# 280109_Button_PCB_4_0.net
KiCad netlist of a schematic drawn in EAGLE
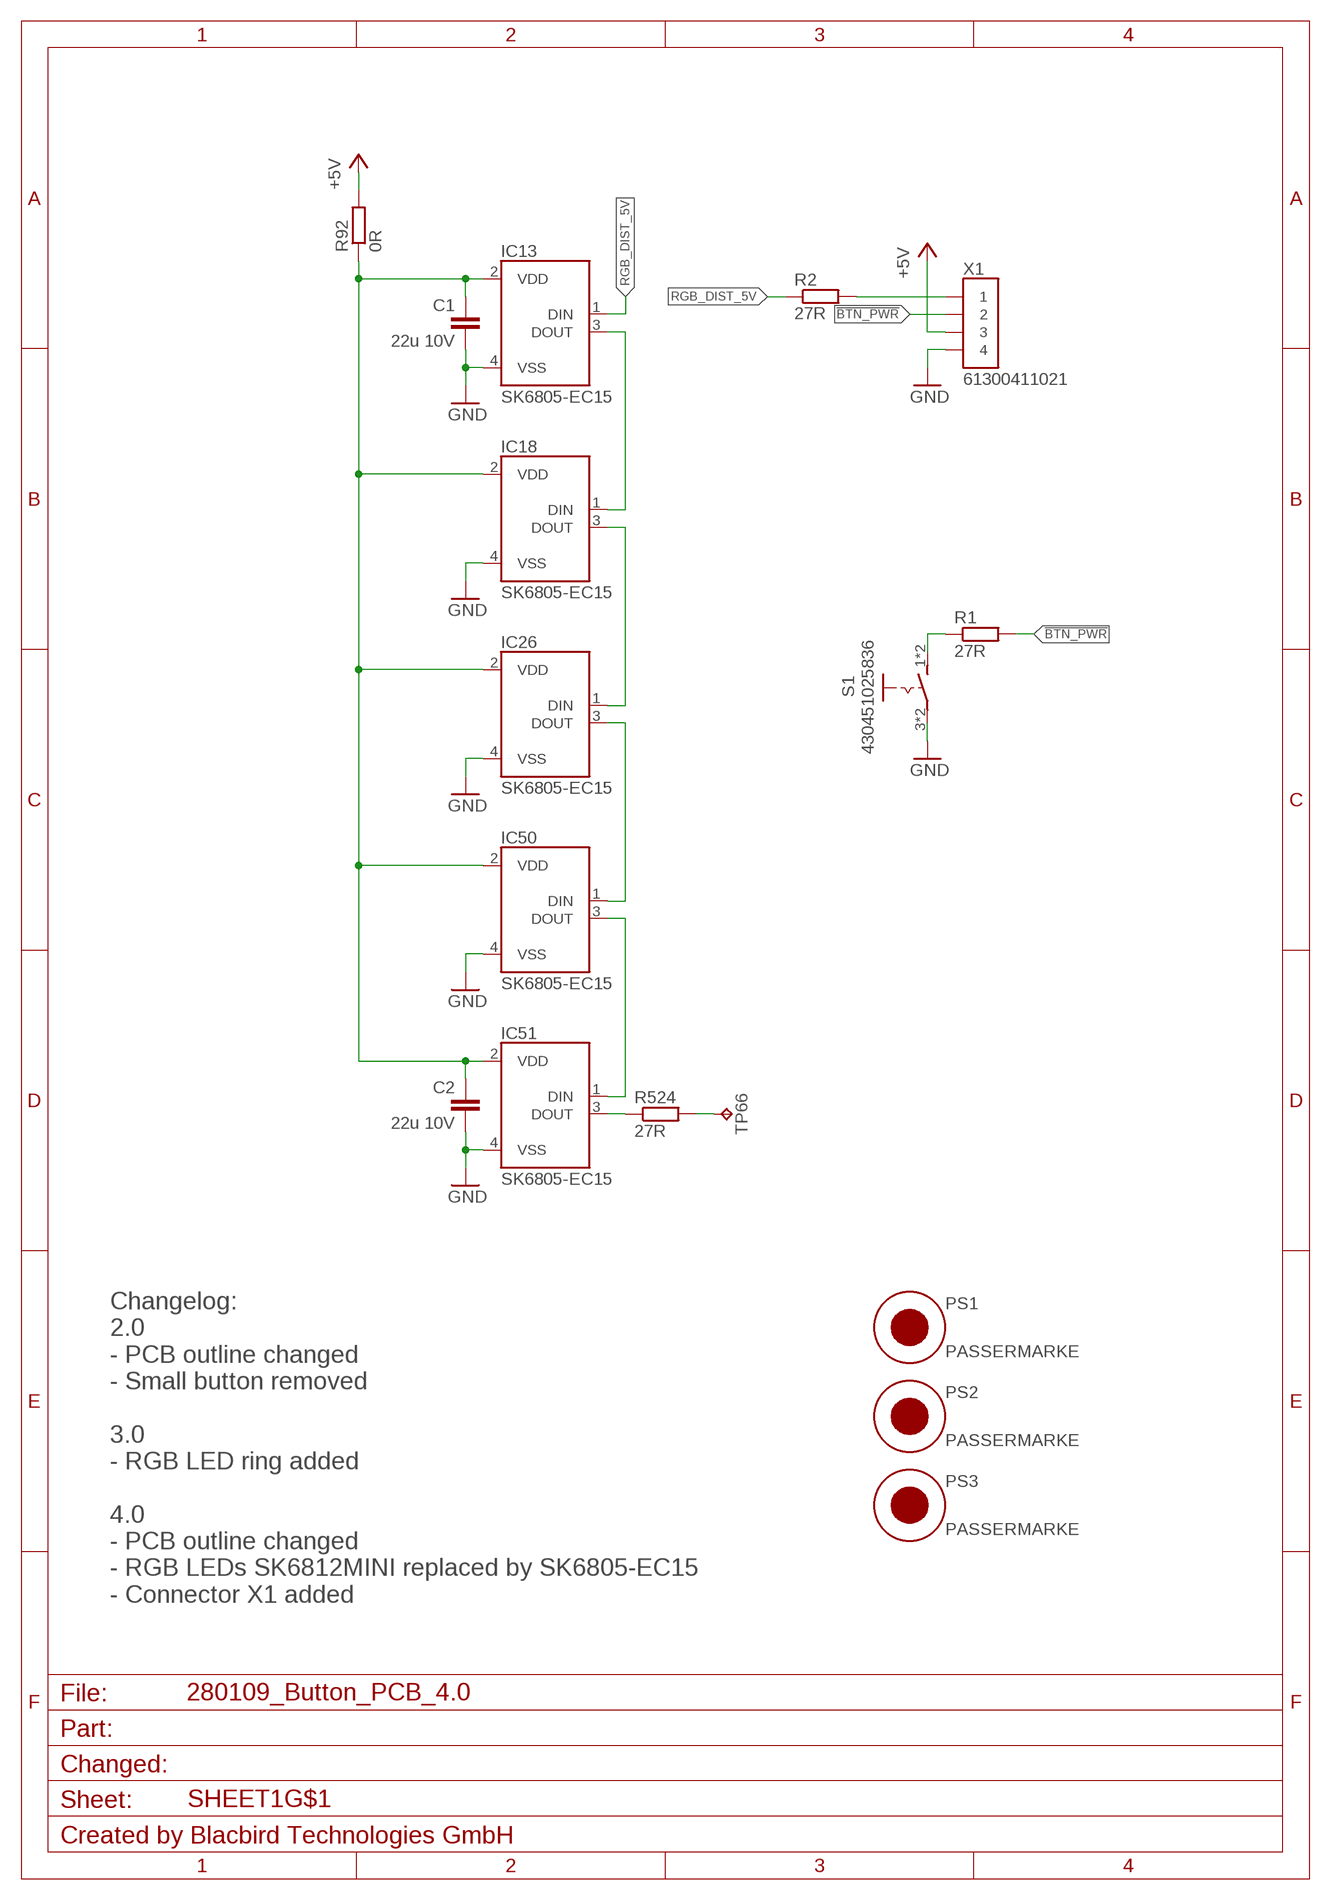
[diagram p0: schematic, sheet 1]

(export (version "E")
  (design (tool "Eeschema 10.0.6"))
  (components
    (comp (ref "C1")
      (value "22u 10V")
      (footprint "eagle-import:C0805")
      (fields (field (name "TOLERANCE") "±20 %") (field (name "VOLTAGE") "10.0 V"))
      (libsource (lib "eagle-import") (part "C-EUC0805"))
    )
    (comp (ref "C2")
      (value "22u 10V")
      (footprint "eagle-import:C0805")
      (fields (field (name "TOLERANCE") "±20 %") (field (name "VOLTAGE") "10.0 V"))
      (libsource (lib "eagle-import") (part "C-EUC0805"))
    )
    (comp (ref "IC13")
      (value "SK6805-EC15")
      (footprint "eagle-import:SK6805-EC_IPIXEL")
      (fields (field (name "MANUFACTURER") "IPIXELS") (field (name "VOLTAGE") "5.5 V"))
      (libsource (lib "eagle-import") (part "SK6805-EC15"))
    )
    (comp (ref "IC18")
      (value "SK6805-EC15")
      (footprint "eagle-import:SK6805-EC_IPIXEL")
      (fields (field (name "MANUFACTURER") "IPIXELS") (field (name "VOLTAGE") "5.5 V"))
      (libsource (lib "eagle-import") (part "SK6805-EC15"))
    )
    (comp (ref "IC26")
      (value "SK6805-EC15")
      (footprint "eagle-import:SK6805-EC_IPIXEL")
      (fields (field (name "MANUFACTURER") "IPIXELS") (field (name "VOLTAGE") "5.5 V"))
      (libsource (lib "eagle-import") (part "SK6805-EC15"))
    )
    (comp (ref "IC50")
      (value "SK6805-EC15")
      (footprint "eagle-import:SK6805-EC_IPIXEL")
      (fields (field (name "MANUFACTURER") "IPIXELS") (field (name "VOLTAGE") "5.5 V"))
      (libsource (lib "eagle-import") (part "SK6805-EC15"))
    )
    (comp (ref "IC51")
      (value "SK6805-EC15")
      (footprint "eagle-import:SK6805-EC_IPIXEL")
      (fields (field (name "MANUFACTURER") "IPIXELS") (field (name "VOLTAGE") "5.5 V"))
      (libsource (lib "eagle-import") (part "SK6805-EC15"))
    )
    (comp (ref "PS1")
      (value "PASSERMARKE")
      (footprint "eagle-import:PASSERMARKE")
      (libsource (lib "eagle-import") (part "PASSERMARKE"))
    )
    (comp (ref "PS2")
      (value "PASSERMARKE")
      (footprint "eagle-import:PASSERMARKE")
      (libsource (lib "eagle-import") (part "PASSERMARKE"))
    )
    (comp (ref "PS3")
      (value "PASSERMARKE")
      (footprint "eagle-import:PASSERMARKE")
      (libsource (lib "eagle-import") (part "PASSERMARKE"))
    )
    (comp (ref "R1")
      (value "27R")
      (footprint "eagle-import:R0603")
      (fields
        (field (name "POWER") "63 mW")
        (field (name "TOLERANCE") "±1 %")
        (field (name "VOLTAGE") "50 V")
      )
      (libsource (lib "eagle-import") (part "R-EUR0603"))
    )
    (comp (ref "R2")
      (value "27R")
      (footprint "eagle-import:R0603")
      (fields
        (field (name "POWER") "63 mW")
        (field (name "TOLERANCE") "±1 %")
        (field (name "VOLTAGE") "50 V")
      )
      (libsource (lib "eagle-import") (part "R-EUR0603"))
    )
    (comp (ref "R92")
      (value "0R")
      (footprint "eagle-import:R0603")
      (fields
        (field (name "POWER") "63 mW")
        (field (name "TOLERANCE") "±1 %")
        (field (name "VOLTAGE") "50 V")
      )
      (libsource (lib "eagle-import") (part "R-EUR0603"))
    )
    (comp (ref "R524")
      (value "27R")
      (footprint "eagle-import:R0603")
      (fields
        (field (name "POWER") "63 mW")
        (field (name "TOLERANCE") "±1 %")
        (field (name "VOLTAGE") "50 V")
      )
      (libsource (lib "eagle-import") (part "R-EUR0603"))
    )
    (comp (ref "S1")
      (value "430451025836")
      (footprint "eagle-import:430451025836_WUERTH")
      (fields (field (name "MANUFACTURER") "Wuerth") (field (name "VOLTAGE") "12.0 V"))
      (libsource (lib "eagle-import") (part "430451025836"))
    )
    (comp (ref "TP66")
      (value "TESTPOINT_VIA_ROUND_0.8MM")
      (footprint "eagle-import:TESTVIA_ROUND_0.8MM")
      (libsource (lib "eagle-import") (part "TESTPOINT_VIA_ROUND_0.8MM"))
    )
    (comp (ref "X1")
      (value "61300411021")
      (footprint "eagle-import:61300411021_WUERTH")
      (fields (field (name "MANUFACTURER") "Wuerth") (field (name "VOLTAGE") "500 V(AC)"))
      (libsource (lib "eagle-import") (part "61300411021"))
    )
  )
  (nets
    (net (code "1") (name "+5V") (class "Default")
      (node (ref "R92") (pin "2") (pinfunction "2_2") (pintype "passive"))
      (node (ref "X1") (pin "3") (pinfunction "3_3") (pintype "passive"))
    )
    (net (code "2") (name "/~{BTN_PWR}") (class "Default")
      (node (ref "R1") (pin "2") (pinfunction "2_2") (pintype "passive"))
      (node (ref "X1") (pin "2") (pinfunction "2_2") (pintype "passive"))
    )
    (net (code "3") (name "GND") (class "Default")
      (node (ref "C1") (pin "2") (pinfunction "2_2") (pintype "passive"))
      (node (ref "C2") (pin "2") (pinfunction "2_2") (pintype "passive"))
      (node (ref "IC13") (pin "4") (pinfunction "VSS_4") (pintype "input"))
      (node (ref "IC18") (pin "4") (pinfunction "VSS_4") (pintype "input"))
      (node (ref "IC26") (pin "4") (pinfunction "VSS_4") (pintype "input"))
      (node (ref "IC50") (pin "4") (pinfunction "VSS_4") (pintype "input"))
      (node (ref "IC51") (pin "4") (pinfunction "VSS_4") (pintype "input"))
      (node (ref "S1") (pin "3") (pinfunction "P_3") (pintype "passive"))
      (node (ref "S1") (pin "4") (pinfunction "P_4") (pintype "passive"))
      (node (ref "X1") (pin "4") (pinfunction "4_4") (pintype "passive"))
    )
    (net (code "4") (name "Net-(IC13-DOUT)") (class "Default")
      (node (ref "IC13") (pin "3") (pinfunction "DOUT_3") (pintype "output"))
      (node (ref "IC18") (pin "1") (pinfunction "DIN_1") (pintype "input"))
    )
    (net (code "5") (name "Net-(IC13-VDD)") (class "Default")
      (node (ref "C1") (pin "1") (pinfunction "1_1") (pintype "passive"))
      (node (ref "C2") (pin "1") (pinfunction "1_1") (pintype "passive"))
      (node (ref "IC13") (pin "2") (pinfunction "VDD_2") (pintype "input"))
      (node (ref "IC18") (pin "2") (pinfunction "VDD_2") (pintype "input"))
      (node (ref "IC26") (pin "2") (pinfunction "VDD_2") (pintype "input"))
      (node (ref "IC50") (pin "2") (pinfunction "VDD_2") (pintype "input"))
      (node (ref "IC51") (pin "2") (pinfunction "VDD_2") (pintype "input"))
      (node (ref "R92") (pin "1") (pinfunction "1_1") (pintype "passive"))
    )
    (net (code "6") (name "Net-(IC18-DOUT)") (class "Default")
      (node (ref "IC18") (pin "3") (pinfunction "DOUT_3") (pintype "output"))
      (node (ref "IC26") (pin "1") (pinfunction "DIN_1") (pintype "input"))
    )
    (net (code "7") (name "Net-(IC26-DOUT)") (class "Default")
      (node (ref "IC26") (pin "3") (pinfunction "DOUT_3") (pintype "output"))
      (node (ref "IC50") (pin "1") (pinfunction "DIN_1") (pintype "input"))
    )
    (net (code "8") (name "Net-(IC50-DOUT)") (class "Default")
      (node (ref "IC50") (pin "3") (pinfunction "DOUT_3") (pintype "output"))
      (node (ref "IC51") (pin "1") (pinfunction "DIN_1") (pintype "input"))
    )
    (net (code "9") (name "Net-(IC51-DOUT)") (class "Default")
      (node (ref "IC51") (pin "3") (pinfunction "DOUT_3") (pintype "output"))
      (node (ref "R524") (pin "1") (pinfunction "1_1") (pintype "passive"))
    )
    (net (code "10") (name "Net-(R1-Pad1)") (class "Default")
      (node (ref "R1") (pin "1") (pinfunction "1_1") (pintype "passive"))
      (node (ref "S1") (pin "1") (pinfunction "S_1") (pintype "passive"))
      (node (ref "S1") (pin "2") (pinfunction "S_2") (pintype "passive"))
    )
    (net (code "11") (name "Net-(R2-Pad2)") (class "Default")
      (node (ref "R2") (pin "2") (pinfunction "2_2") (pintype "passive"))
      (node (ref "X1") (pin "1") (pinfunction "1_1") (pintype "passive"))
    )
    (net (code "12") (name "Net-(TP66-TP)") (class "Default")
      (node (ref "R524") (pin "2") (pinfunction "2_2") (pintype "passive"))
      (node (ref "TP66") (pin "P$1") (pinfunction "TP_P$1") (pintype "input"))
    )
    (net (code "13") (name "RGB_DIST_5V") (class "Default")
      (node (ref "IC13") (pin "1") (pinfunction "DIN_1") (pintype "input"))
      (node (ref "R2") (pin "1") (pinfunction "1_1") (pintype "passive"))
    )
  )
)
